# RX-FM-Radio-1_5V.net
KiCad netlist of a schematic drawn in EAGLE
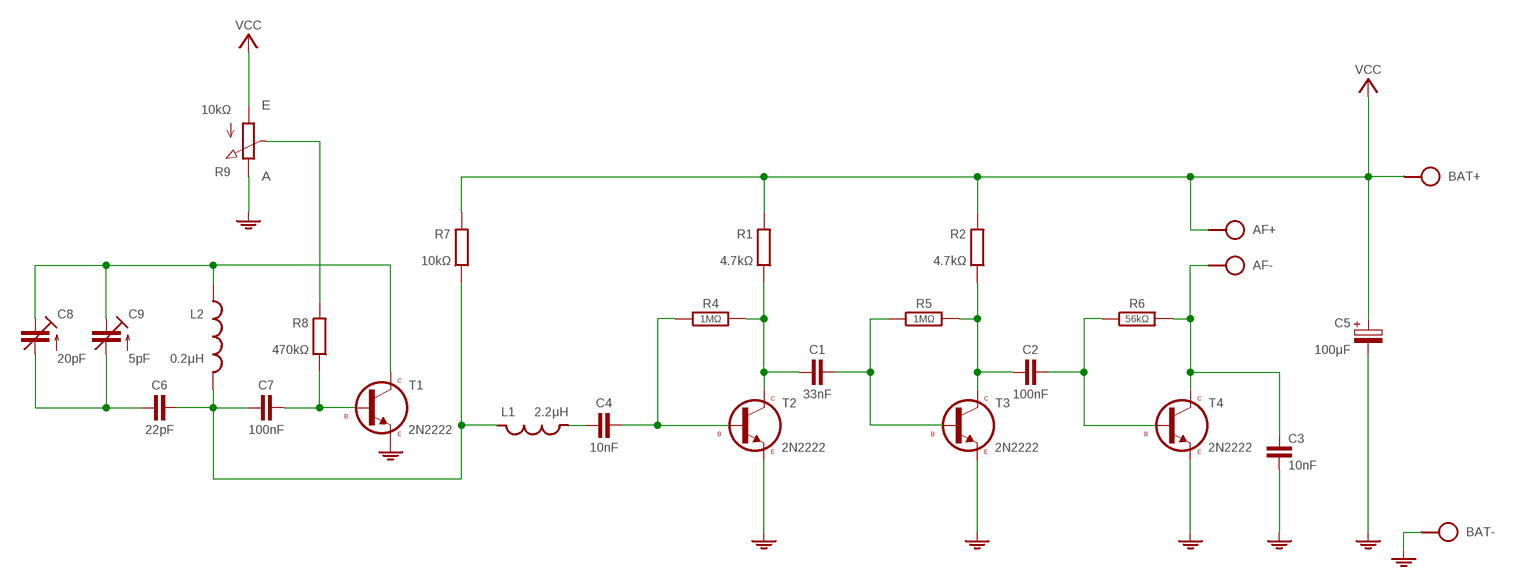
[diagram p0: schematic, sheet 1]

(export (version "E")
  (design (tool "Eeschema 10.0.6"))
  (components
    (comp (ref "AF")
      (value "SPAD+-+-")
      (footprint "eagle-import:SPAD+-")
      (libsource (lib "eagle-import") (part "SPAD+-+-"))
    )
    (comp (ref "BAT")
      (value "SPAD+-+-")
      (footprint "eagle-import:SPAD+-")
      (libsource (lib "eagle-import") (part "SPAD+-+-"))
    )
    (comp (ref "C1")
      (value "33nF")
      (footprint "eagle-import:C050-020X044")
      (libsource (lib "eagle-import") (part "C-H050-020X044"))
    )
    (comp (ref "C2")
      (value "100nF")
      (footprint "eagle-import:C050-020X044")
      (libsource (lib "eagle-import") (part "C-H050-020X044"))
    )
    (comp (ref "C3")
      (value "10nF")
      (footprint "eagle-import:C050-025X060")
      (libsource (lib "eagle-import") (part "C025-025X060"))
    )
    (comp (ref "C4")
      (value "10nF")
      (footprint "eagle-import:C050-020X044")
      (libsource (lib "eagle-import") (part "C-H050-020X044"))
    )
    (comp (ref "C5")
      (value "100μF")
      (footprint "eagle-import:E2.5-4_V")
      (libsource (lib "eagle-import") (part "CPOLE2,5-4/V"))
    )
    (comp (ref "C6")
      (value "22pF")
      (footprint "eagle-import:C050-020X036")
      (libsource (lib "eagle-import") (part "C-H050-020X036"))
    )
    (comp (ref "C7")
      (value "100nF")
      (footprint "eagle-import:C075-020X044")
      (libsource (lib "eagle-import") (part "C-H075-020X044"))
    )
    (comp (ref "C8")
      (value "20pF")
      (footprint "eagle-import:TRIM-2222-808")
      (libsource (lib "eagle-import") (part "C-TR-PH201272222-808-2PIND"))
    )
    (comp (ref "C9")
      (value "5pF")
      (footprint "eagle-import:CTRIMTZ03")
      (libsource (lib "eagle-import") (part "C-TR-PH20127-TZ03"))
    )
    (comp (ref "L1")
      (value "2.2μH")
      (footprint "eagle-import:L-03_10")
      (libsource (lib "eagle-import") (part "L-H-SHORT-03/10"))
    )
    (comp (ref "L2")
      (value "0.2μH")
      (footprint "eagle-import:L-10_10Y")
      (libsource (lib "eagle-import") (part "L10/10Y"))
    )
    (comp (ref "R1")
      (value "4.7kΩ")
      (footprint "eagle-import:0204_10-V")
      (libsource (lib "eagle-import") (part "R0204/10-V"))
    )
    (comp (ref "R2")
      (value "4.7kΩ")
      (footprint "eagle-import:0204_10-V")
      (libsource (lib "eagle-import") (part "R0204/10-V"))
    )
    (comp (ref "R4")
      (value "1MΩ")
      (footprint "eagle-import:0204_10-V")
      (libsource (lib "eagle-import") (part "R-H0204/10-V"))
    )
    (comp (ref "R5")
      (value "1MΩ")
      (footprint "eagle-import:0204_10-V")
      (libsource (lib "eagle-import") (part "R-H0204/10-V"))
    )
    (comp (ref "R6")
      (value "56kΩ")
      (footprint "eagle-import:0204_10-V")
      (libsource (lib "eagle-import") (part "R-H0204/10-V"))
    )
    (comp (ref "R7")
      (value "10kΩ")
      (footprint "eagle-import:0204_10-V")
      (libsource (lib "eagle-import") (part "R0204/10-V"))
    )
    (comp (ref "R8")
      (value "470kΩ")
      (footprint "eagle-import:0204_10-V")
      (libsource (lib "eagle-import") (part "R0204/10-V"))
    )
    (comp (ref "R9")
      (value "10kΩ")
      (footprint "eagle-import:POT")
      (libsource (lib "eagle-import") (part "POT"))
    )
    (comp (ref "T1")
      (value "2N2222")
      (footprint "eagle-import:TO92")
      (libsource (lib "eagle-import") (part "2N2222"))
    )
    (comp (ref "T2")
      (value "2N2222")
      (footprint "eagle-import:TO92")
      (libsource (lib "eagle-import") (part "2N2222"))
    )
    (comp (ref "T3")
      (value "2N2222")
      (footprint "eagle-import:TO92")
      (libsource (lib "eagle-import") (part "2N2222"))
    )
    (comp (ref "T4")
      (value "2N2222")
      (footprint "eagle-import:TO92")
      (libsource (lib "eagle-import") (part "2N2222"))
    )
  )
  (nets
    (net (code "1") (name "GND") (class "Default")
      (node (ref "BAT") (pin "1") (pinfunction "P$1_1") (pintype "passive"))
      (node (ref "C3") (pin "2") (pinfunction "2_2") (pintype "passive"))
      (node (ref "C5") (pin "-") (pinfunction "-_-") (pintype "passive"))
      (node (ref "R9") (pin "E") (pinfunction "E_E") (pintype "passive"))
      (node (ref "T1") (pin "1") (pinfunction "E_1") (pintype "passive"))
      (node (ref "T2") (pin "1") (pinfunction "E_1") (pintype "passive"))
      (node (ref "T3") (pin "1") (pinfunction "E_1") (pintype "passive"))
      (node (ref "T4") (pin "1") (pinfunction "E_1") (pintype "passive"))
    )
    (net (code "2") (name "Net-(AFB-P$1)") (class "Default")
      (node (ref "AF") (pin "1") (pinfunction "P$1_1") (pintype "passive"))
      (node (ref "C3") (pin "1") (pinfunction "1_1") (pintype "passive"))
      (node (ref "R6") (pin "2") (pinfunction "2_2") (pintype "passive"))
      (node (ref "T4") (pin "3") (pinfunction "C_3") (pintype "passive"))
    )
    (net (code "3") (name "Net-(C4-Pad1)") (class "Default")
      (node (ref "C4") (pin "1") (pinfunction "1_1") (pintype "passive"))
      (node (ref "L1") (pin "1") (pinfunction "1_1") (pintype "passive"))
    )
    (net (code "4") (name "Net-(C8-A)") (class "Default")
      (node (ref "C6") (pin "1") (pinfunction "1_1") (pintype "passive"))
      (node (ref "C8") (pin "2") (pinfunction "A_2") (pintype "passive"))
      (node (ref "C9") (pin "1") (pinfunction "A_1") (pintype "passive"))
    )
    (net (code "5") (name "Net-(C8-E)") (class "Default")
      (node (ref "C8") (pin "3") (pinfunction "E_3") (pintype "passive"))
      (node (ref "C9") (pin "2") (pinfunction "E_2") (pintype "passive"))
      (node (ref "L2") (pin "P$1") (pinfunction "1_P$1") (pintype "passive"))
      (node (ref "T1") (pin "3") (pinfunction "C_3") (pintype "passive"))
    )
    (net (code "6") (name "Net-(L2-2)") (class "Default")
      (node (ref "C6") (pin "2") (pinfunction "2_2") (pintype "passive"))
      (node (ref "C7") (pin "1") (pinfunction "1_1") (pintype "passive"))
      (node (ref "L1") (pin "2") (pinfunction "2_2") (pintype "passive"))
      (node (ref "L2") (pin "P$2") (pinfunction "2_P$2") (pintype "passive"))
      (node (ref "R7") (pin "2") (pinfunction "1_2") (pintype "passive"))
    )
    (net (code "7") (name "Net-(R1-1)") (class "Default")
      (node (ref "C1") (pin "1") (pinfunction "1_1") (pintype "passive"))
      (node (ref "R1") (pin "2") (pinfunction "1_2") (pintype "passive"))
      (node (ref "R4") (pin "2") (pinfunction "2_2") (pintype "passive"))
      (node (ref "T2") (pin "3") (pinfunction "C_3") (pintype "passive"))
    )
    (net (code "8") (name "Net-(R2-1)") (class "Default")
      (node (ref "C2") (pin "1") (pinfunction "1_1") (pintype "passive"))
      (node (ref "R2") (pin "2") (pinfunction "1_2") (pintype "passive"))
      (node (ref "R5") (pin "2") (pinfunction "2_2") (pintype "passive"))
      (node (ref "T3") (pin "3") (pinfunction "C_3") (pintype "passive"))
    )
    (net (code "9") (name "Net-(R8-1)") (class "Default")
      (node (ref "C7") (pin "2") (pinfunction "2_2") (pintype "passive"))
      (node (ref "R8") (pin "2") (pinfunction "1_2") (pintype "passive"))
      (node (ref "T1") (pin "2") (pinfunction "B_2") (pintype "passive"))
    )
    (net (code "10") (name "Net-(R8-2)") (class "Default")
      (node (ref "R8") (pin "1") (pinfunction "2_1") (pintype "passive"))
      (node (ref "R9") (pin "S") (pinfunction "S_S") (pintype "passive"))
    )
    (net (code "11") (name "Net-(T2-B)") (class "Default")
      (node (ref "C4") (pin "2") (pinfunction "2_2") (pintype "passive"))
      (node (ref "R4") (pin "1") (pinfunction "1_1") (pintype "passive"))
      (node (ref "T2") (pin "2") (pinfunction "B_2") (pintype "passive"))
    )
    (net (code "12") (name "Net-(T3-B)") (class "Default")
      (node (ref "C1") (pin "2") (pinfunction "2_2") (pintype "passive"))
      (node (ref "R5") (pin "1") (pinfunction "1_1") (pintype "passive"))
      (node (ref "T3") (pin "2") (pinfunction "B_2") (pintype "passive"))
    )
    (net (code "13") (name "Net-(T4-B)") (class "Default")
      (node (ref "C2") (pin "2") (pinfunction "2_2") (pintype "passive"))
      (node (ref "R6") (pin "1") (pinfunction "1_1") (pintype "passive"))
      (node (ref "T4") (pin "2") (pinfunction "B_2") (pintype "passive"))
    )
    (net (code "14") (name "VCC") (class "Default")
      (node (ref "AF") (pin "2") (pinfunction "P$1_2") (pintype "passive"))
      (node (ref "BAT") (pin "2") (pinfunction "P$1_2") (pintype "passive"))
      (node (ref "C5") (pin "+") (pinfunction "+_+") (pintype "passive"))
      (node (ref "R1") (pin "1") (pinfunction "2_1") (pintype "passive"))
      (node (ref "R2") (pin "1") (pinfunction "2_1") (pintype "passive"))
      (node (ref "R7") (pin "1") (pinfunction "2_1") (pintype "passive"))
      (node (ref "R9") (pin "A") (pinfunction "A_A") (pintype "passive"))
    )
  )
)
